# RN4020F-2A.net
KiCad netlist of a schematic drawn in EAGLE
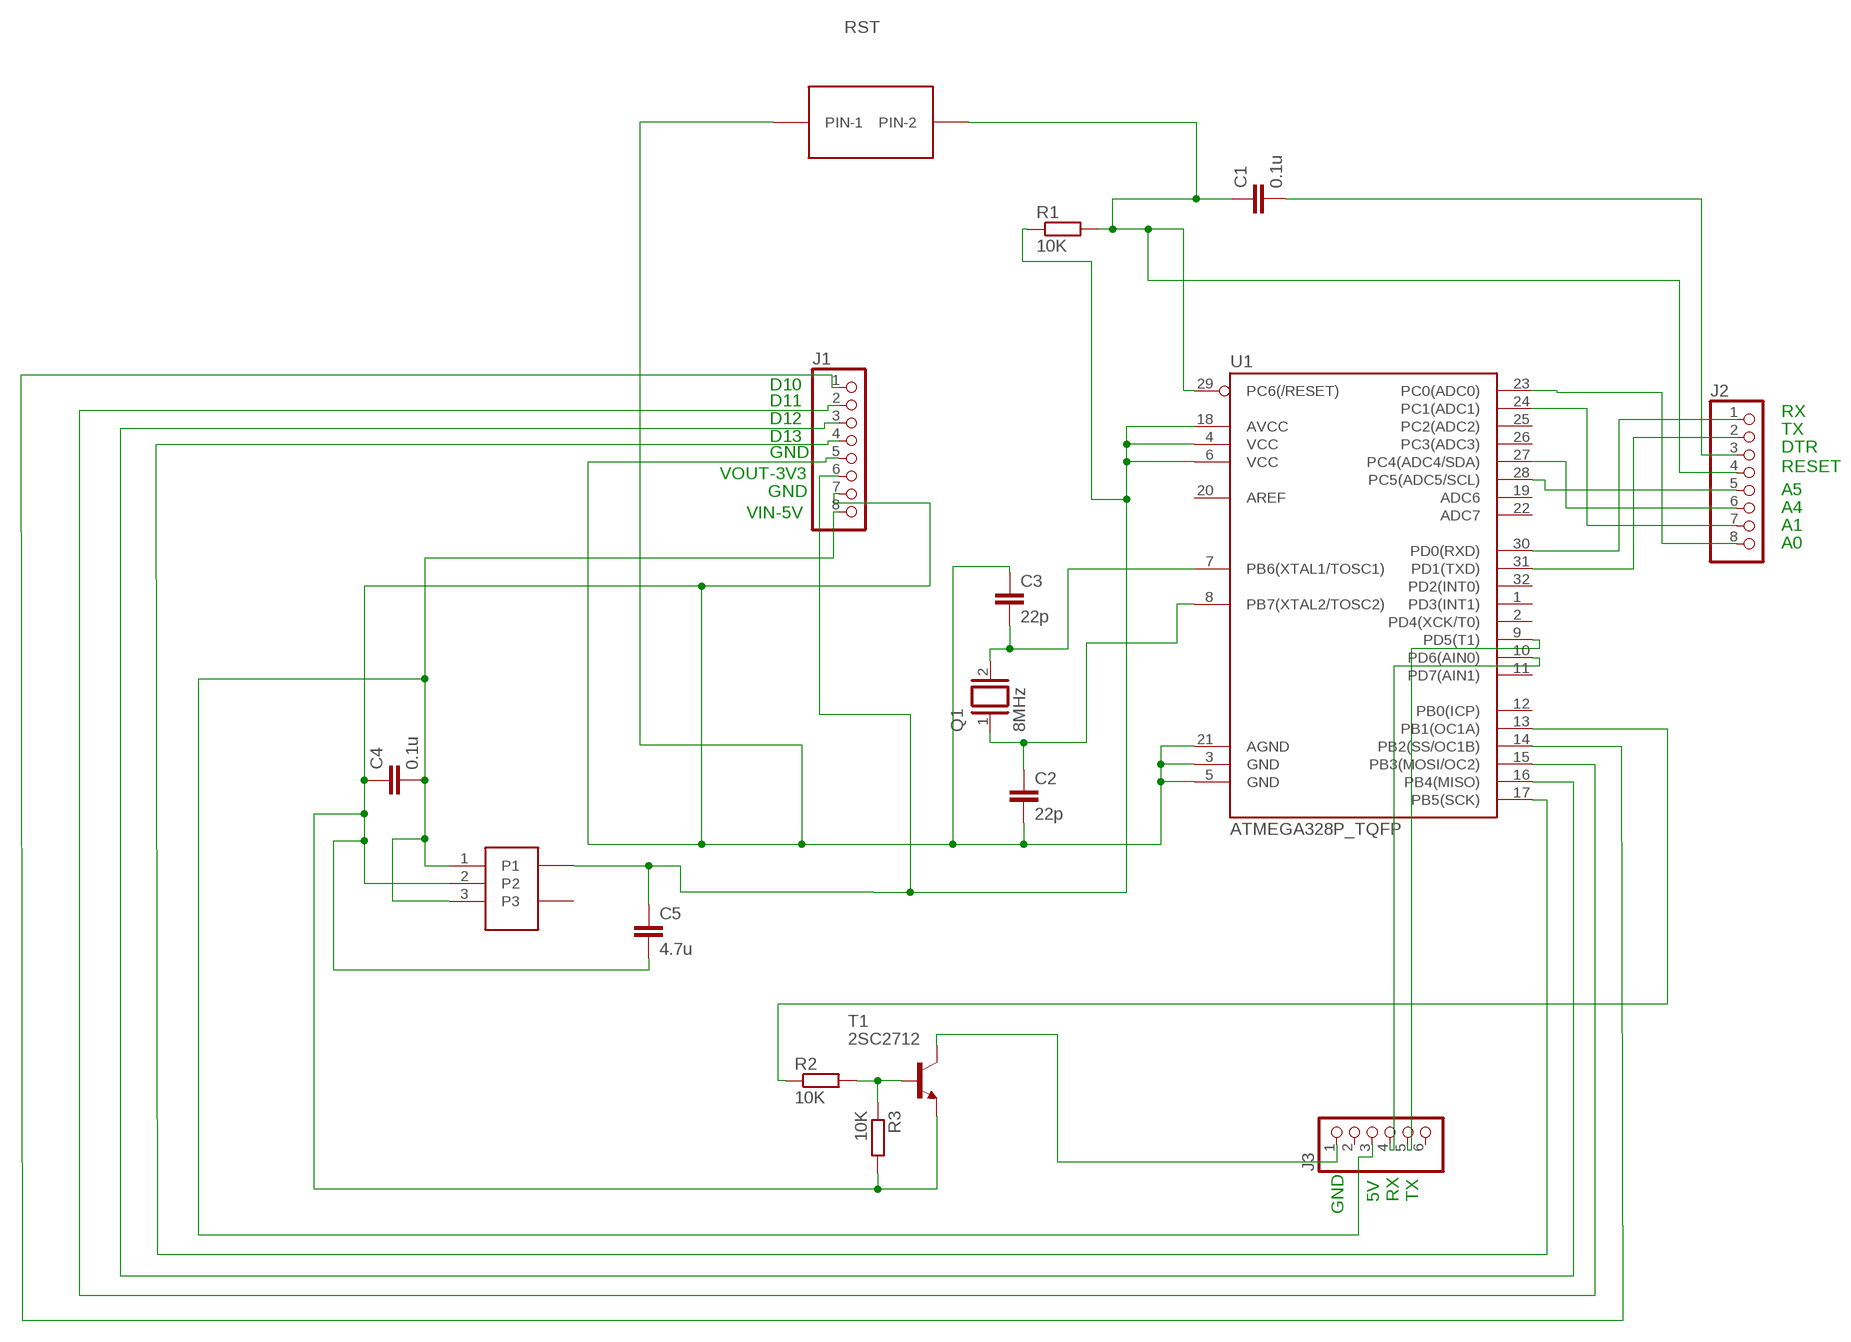
[diagram p0: schematic, sheet 1]

(export (version "E")
  (design (tool "Eeschema 10.0.6"))
  (components
    (comp (ref "C1")
      (value "0.1u")
      (footprint "eagle-import:C0603")
      (libsource (lib "eagle-import") (part "C-EUC0603"))
    )
    (comp (ref "C2")
      (value "22p")
      (footprint "eagle-import:C0603")
      (libsource (lib "eagle-import") (part "C-EUC0603"))
    )
    (comp (ref "C3")
      (value "22p")
      (footprint "eagle-import:C0603")
      (libsource (lib "eagle-import") (part "C-EUC0603"))
    )
    (comp (ref "C4")
      (value "0.1u")
      (footprint "eagle-import:C0603")
      (libsource (lib "eagle-import") (part "C-EUC0603"))
    )
    (comp (ref "C5")
      (value "4.7u")
      (footprint "eagle-import:C1206")
      (libsource (lib "eagle-import") (part "C-EUC1206"))
    )
    (comp (ref "J1")
      (value "PINHD-1X8")
      (footprint "eagle-import:1X08")
      (libsource (lib "eagle-import") (part "PINHD-1X8"))
    )
    (comp (ref "J2")
      (value "PINHD-1X8")
      (footprint "eagle-import:1X08")
      (libsource (lib "eagle-import") (part "PINHD-1X8"))
    )
    (comp (ref "J3")
      (value "PINHD-1X6")
      (footprint "eagle-import:1X06")
      (libsource (lib "eagle-import") (part "PINHD-1X6"))
    )
    (comp (ref "Q1")
      (value "8MHz")
      (footprint "eagle-import:QS")
      (libsource (lib "eagle-import") (part "XTAL/S"))
    )
    (comp (ref "R1")
      (value "10K")
      (footprint "eagle-import:R0603")
      (libsource (lib "eagle-import") (part "R-EU_R0603"))
    )
    (comp (ref "R2")
      (value "10K")
      (footprint "eagle-import:R0603")
      (libsource (lib "eagle-import") (part "R-EU_R0603"))
    )
    (comp (ref "R3")
      (value "10K")
      (footprint "eagle-import:R0603")
      (libsource (lib "eagle-import") (part "R-EU_R0603"))
    )
    (comp (ref "RST")
      (value "BTN2-EX")
      (footprint "eagle-import:B3F-10XX")
      (libsource (lib "eagle-import") (part "BTN2-EX"))
    )
    (comp (ref "T1")
      (value "2SC2712")
      (footprint "eagle-import:SOT23")
      (libsource (lib "eagle-import") (part "BC846"))
    )
    (comp (ref "U1")
      (value "ATMEGA328P_TQFP")
      (footprint "eagle-import:TQFP32-08")
      (libsource (lib "eagle-import") (part "ATMEGA328P_TQFP"))
    )
    (comp (ref "U2")
      (value "NJM2866F33")
      (footprint "eagle-import:SOT23-3")
      (libsource (lib "eagle-import") (part "NJM2866F33"))
    )
  )
  (nets
    (net (code "1") (name "Net-(C1-Pad2)") (class "Default")
      (node (ref "C1") (pin "2") (pinfunction "2_2") (pintype "passive"))
      (node (ref "J2") (pin "3") (pinfunction "3_3") (pintype "passive"))
    )
    (net (code "2") (name "Net-(RST-PIN-1)") (class "Default")
      (node (ref "C2") (pin "2") (pinfunction "2_2") (pintype "passive"))
      (node (ref "C3") (pin "1") (pinfunction "1_1") (pintype "passive"))
      (node (ref "C4") (pin "1") (pinfunction "1_1") (pintype "passive"))
      (node (ref "C5") (pin "2") (pinfunction "2_2") (pintype "passive"))
      (node (ref "J1") (pin "5") (pinfunction "5_5") (pintype "passive"))
      (node (ref "J1") (pin "7") (pinfunction "7_7") (pintype "passive"))
      (node (ref "R3") (pin "2") (pinfunction "2_2") (pintype "passive"))
      (node (ref "RST") (pin "1") (pinfunction "PIN-1_1") (pintype "bidirectional"))
      (node (ref "T1") (pin "2") (pinfunction "E_2") (pintype "passive"))
      (node (ref "U1") (pin "21") (pinfunction "AGND_21") (pintype "bidirectional"))
      (node (ref "U1") (pin "3") (pinfunction "GND_3") (pintype "bidirectional"))
      (node (ref "U1") (pin "5") (pinfunction "GND_5") (pintype "bidirectional"))
      (node (ref "U2") (pin "2") (pinfunction "P2_2") (pintype "bidirectional"))
    )
    (net (code "3") (name "Net-(RST-PIN-2)") (class "Default")
      (node (ref "C1") (pin "1") (pinfunction "1_1") (pintype "passive"))
      (node (ref "J2") (pin "4") (pinfunction "4_4") (pintype "passive"))
      (node (ref "R1") (pin "2") (pinfunction "2_2") (pintype "passive"))
      (node (ref "RST") (pin "2") (pinfunction "PIN-2_2") (pintype "bidirectional"))
      (node (ref "U1") (pin "29") (pinfunction "PC6(/RESET)_29") (pintype "bidirectional"))
    )
    (net (code "4") (name "Net-(T1-B)") (class "Default")
      (node (ref "R2") (pin "2") (pinfunction "2_2") (pintype "passive"))
      (node (ref "R3") (pin "1") (pinfunction "1_1") (pintype "passive"))
      (node (ref "T1") (pin "1") (pinfunction "B_1") (pintype "passive"))
    )
    (net (code "5") (name "Net-(T1-C)") (class "Default")
      (node (ref "J3") (pin "1") (pinfunction "1_1") (pintype "passive"))
      (node (ref "T1") (pin "3") (pinfunction "C_3") (pintype "passive"))
    )
    (net (code "6") (name "Net-(U1-AVCC)") (class "Default")
      (node (ref "C5") (pin "1") (pinfunction "1_1") (pintype "passive"))
      (node (ref "J1") (pin "6") (pinfunction "6_6") (pintype "passive"))
      (node (ref "R1") (pin "1") (pinfunction "1_1") (pintype "passive"))
      (node (ref "U1") (pin "18") (pinfunction "AVCC_18") (pintype "bidirectional"))
      (node (ref "U1") (pin "4") (pinfunction "VCC_4") (pintype "bidirectional"))
      (node (ref "U1") (pin "6") (pinfunction "VCC_6") (pintype "bidirectional"))
      (node (ref "U2") (pin "5") (pinfunction "P5_5") (pintype "bidirectional"))
    )
    (net (code "7") (name "Net-(U1-PB1(OC1A))") (class "Default")
      (node (ref "R2") (pin "1") (pinfunction "1_1") (pintype "passive"))
      (node (ref "U1") (pin "13") (pinfunction "PB1(OC1A)_13") (pintype "bidirectional"))
    )
    (net (code "8") (name "Net-(U1-PB2(SS{slash}OC1B))") (class "Default")
      (node (ref "J1") (pin "1") (pinfunction "1_1") (pintype "passive"))
      (node (ref "U1") (pin "14") (pinfunction "PB2(SS/OC1B)_14") (pintype "bidirectional"))
    )
    (net (code "9") (name "Net-(U1-PB3(MOSI{slash}OC2))") (class "Default")
      (node (ref "J1") (pin "2") (pinfunction "2_2") (pintype "passive"))
      (node (ref "U1") (pin "15") (pinfunction "PB3(MOSI/OC2)_15") (pintype "bidirectional"))
    )
    (net (code "10") (name "Net-(U1-PB4(MISO))") (class "Default")
      (node (ref "J1") (pin "3") (pinfunction "3_3") (pintype "passive"))
      (node (ref "U1") (pin "16") (pinfunction "PB4(MISO)_16") (pintype "bidirectional"))
    )
    (net (code "11") (name "Net-(U1-PB5(SCK))") (class "Default")
      (node (ref "J1") (pin "4") (pinfunction "4_4") (pintype "passive"))
      (node (ref "U1") (pin "17") (pinfunction "PB5(SCK)_17") (pintype "bidirectional"))
    )
    (net (code "12") (name "Net-(U1-PB6(XTAL1{slash}TOSC1))") (class "Default")
      (node (ref "C3") (pin "2") (pinfunction "2_2") (pintype "passive"))
      (node (ref "Q1") (pin "2") (pinfunction "2_2") (pintype "passive"))
      (node (ref "U1") (pin "7") (pinfunction "PB6(XTAL1/TOSC1)_7") (pintype "bidirectional"))
    )
    (net (code "13") (name "Net-(U1-PB7(XTAL2{slash}TOSC2))") (class "Default")
      (node (ref "C2") (pin "1") (pinfunction "1_1") (pintype "passive"))
      (node (ref "Q1") (pin "1") (pinfunction "1_1") (pintype "passive"))
      (node (ref "U1") (pin "8") (pinfunction "PB7(XTAL2/TOSC2)_8") (pintype "bidirectional"))
    )
    (net (code "14") (name "Net-(U1-PC0(ADC0))") (class "Default")
      (node (ref "J2") (pin "8") (pinfunction "8_8") (pintype "passive"))
      (node (ref "U1") (pin "23") (pinfunction "PC0(ADC0)_23") (pintype "bidirectional"))
    )
    (net (code "15") (name "Net-(U1-PC1(ADC1))") (class "Default")
      (node (ref "J2") (pin "7") (pinfunction "7_7") (pintype "passive"))
      (node (ref "U1") (pin "24") (pinfunction "PC1(ADC1)_24") (pintype "bidirectional"))
    )
    (net (code "16") (name "Net-(U1-PC4(ADC4{slash}SDA))") (class "Default")
      (node (ref "J2") (pin "6") (pinfunction "6_6") (pintype "passive"))
      (node (ref "U1") (pin "27") (pinfunction "PC4(ADC4/SDA)_27") (pintype "bidirectional"))
    )
    (net (code "17") (name "Net-(U1-PC5(ADC5{slash}SCL))") (class "Default")
      (node (ref "J2") (pin "5") (pinfunction "5_5") (pintype "passive"))
      (node (ref "U1") (pin "28") (pinfunction "PC5(ADC5/SCL)_28") (pintype "bidirectional"))
    )
    (net (code "18") (name "Net-(U1-PD0(RXD))") (class "Default")
      (node (ref "J2") (pin "1") (pinfunction "1_1") (pintype "passive"))
      (node (ref "U1") (pin "30") (pinfunction "PD0(RXD)_30") (pintype "bidirectional"))
    )
    (net (code "19") (name "Net-(U1-PD1(TXD))") (class "Default")
      (node (ref "J2") (pin "2") (pinfunction "2_2") (pintype "passive"))
      (node (ref "U1") (pin "31") (pinfunction "PD1(TXD)_31") (pintype "bidirectional"))
    )
    (net (code "20") (name "Net-(U1-PD5(T1))") (class "Default")
      (node (ref "J3") (pin "5") (pinfunction "5_5") (pintype "passive"))
      (node (ref "U1") (pin "9") (pinfunction "PD5(T1)_9") (pintype "bidirectional"))
    )
    (net (code "21") (name "Net-(U1-PD6(AIN0))") (class "Default")
      (node (ref "J3") (pin "4") (pinfunction "4_4") (pintype "passive"))
      (node (ref "U1") (pin "10") (pinfunction "PD6(AIN0)_10") (pintype "bidirectional"))
    )
    (net (code "22") (name "Net-(U2-P1)") (class "Default")
      (node (ref "C4") (pin "2") (pinfunction "2_2") (pintype "passive"))
      (node (ref "J1") (pin "8") (pinfunction "8_8") (pintype "passive"))
      (node (ref "J3") (pin "3") (pinfunction "3_3") (pintype "passive"))
      (node (ref "U2") (pin "1") (pinfunction "P1_1") (pintype "bidirectional"))
      (node (ref "U2") (pin "3") (pinfunction "P3_3") (pintype "bidirectional"))
    )
    (net (code "23") (name "unconnected-(J3-Pad2)") (class "Default")
      (node (ref "J3") (pin "2") (pinfunction "2_2") (pintype "passive"))
    )
    (net (code "24") (name "unconnected-(J3-Pad6)") (class "Default")
      (node (ref "J3") (pin "6") (pinfunction "6_6") (pintype "passive"))
    )
    (net (code "25") (name "unconnected-(U1-ADC6-Pad19)") (class "Default")
      (node (ref "U1") (pin "19") (pinfunction "ADC6_19") (pintype "bidirectional"))
    )
    (net (code "26") (name "unconnected-(U1-ADC7-Pad22)") (class "Default")
      (node (ref "U1") (pin "22") (pinfunction "ADC7_22") (pintype "bidirectional"))
    )
    (net (code "27") (name "unconnected-(U1-AREF-Pad20)") (class "Default")
      (node (ref "U1") (pin "20") (pinfunction "AREF_20") (pintype "bidirectional"))
    )
    (net (code "28") (name "unconnected-(U1-PB0(ICP)-Pad12)") (class "Default")
      (node (ref "U1") (pin "12") (pinfunction "PB0(ICP)_12") (pintype "bidirectional"))
    )
    (net (code "29") (name "unconnected-(U1-PC2(ADC2)-Pad25)") (class "Default")
      (node (ref "U1") (pin "25") (pinfunction "PC2(ADC2)_25") (pintype "bidirectional"))
    )
    (net (code "30") (name "unconnected-(U1-PC3(ADC3)-Pad26)") (class "Default")
      (node (ref "U1") (pin "26") (pinfunction "PC3(ADC3)_26") (pintype "bidirectional"))
    )
    (net (code "31") (name "unconnected-(U1-PD2(INT0)-Pad32)") (class "Default")
      (node (ref "U1") (pin "32") (pinfunction "PD2(INT0)_32") (pintype "bidirectional"))
    )
    (net (code "32") (name "unconnected-(U1-PD3(INT1)-Pad1)") (class "Default")
      (node (ref "U1") (pin "1") (pinfunction "PD3(INT1)_1") (pintype "bidirectional"))
    )
    (net (code "33") (name "unconnected-(U1-PD4(XCK{slash}T0)-Pad2)") (class "Default")
      (node (ref "U1") (pin "2") (pinfunction "PD4(XCK/T0)_2") (pintype "bidirectional"))
    )
    (net (code "34") (name "unconnected-(U1-PD7(AIN1)-Pad11)") (class "Default")
      (node (ref "U1") (pin "11") (pinfunction "PD7(AIN1)_11") (pintype "bidirectional"))
    )
    (net (code "35") (name "unconnected-(U2-P4-Pad4)") (class "Default")
      (node (ref "U2") (pin "4") (pinfunction "P4_4") (pintype "bidirectional"))
    )
  )
)
